# in-14driver.net
KiCad netlist of a schematic drawn in EAGLE
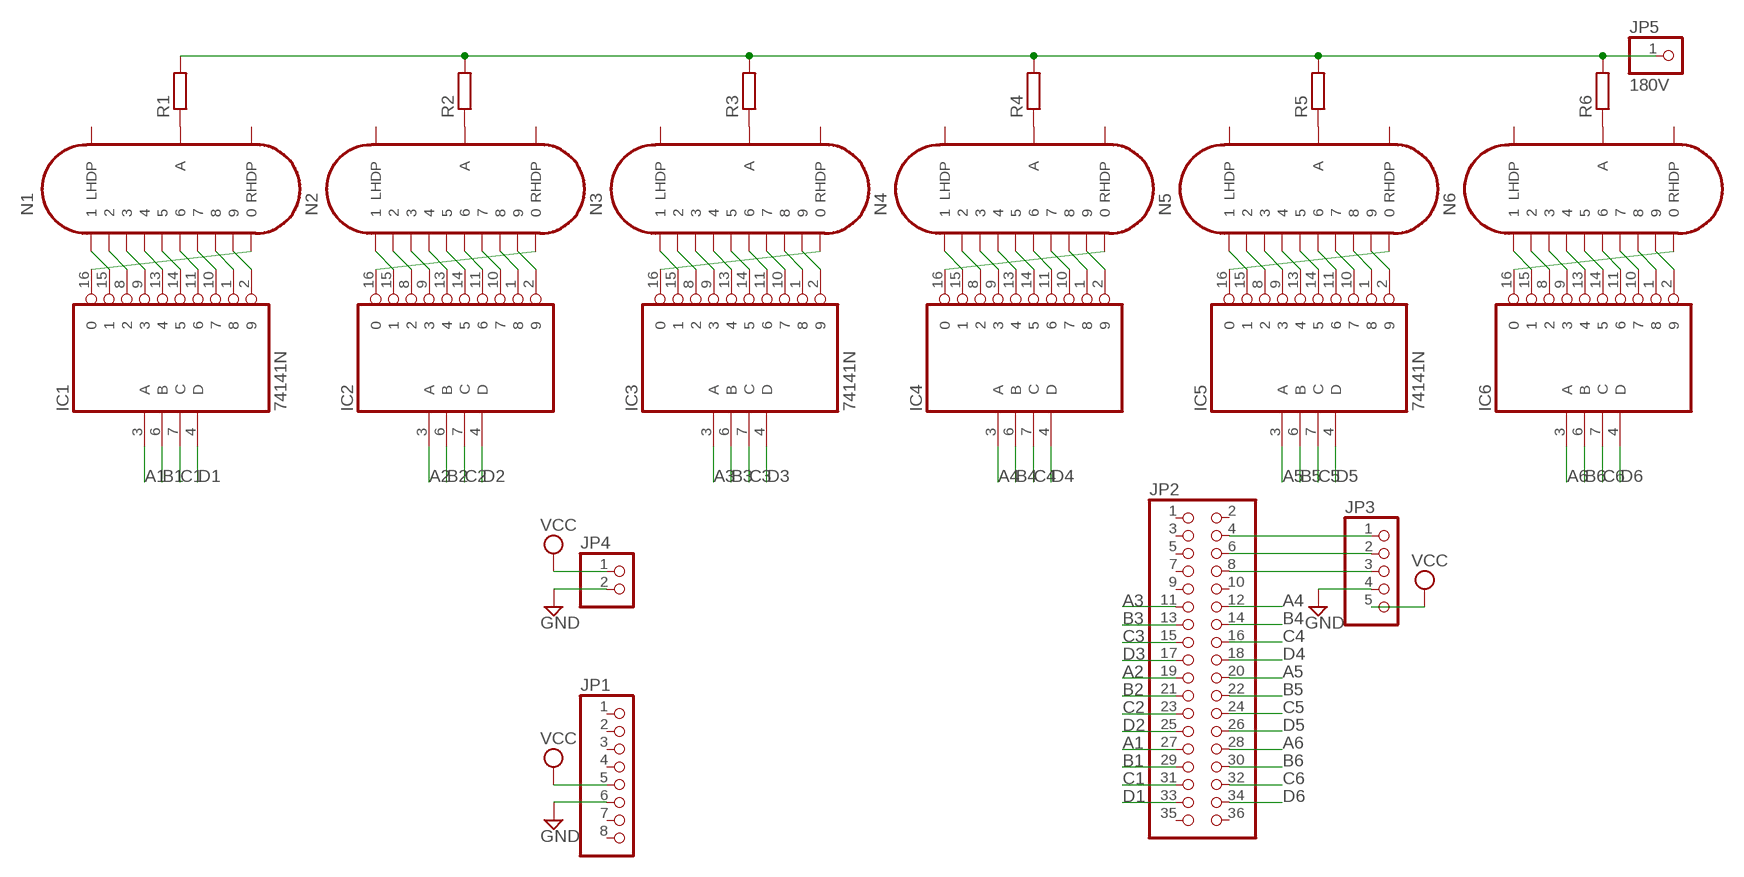
[diagram p0: schematic, sheet 1]

(export (version "E")
  (design (tool "Eeschema 10.0.6"))
  (components
    (comp (ref "IC1")
      (value "74141N")
      (footprint "eagle-import:DIL16")
      (libsource (lib "eagle-import") (part "74141N"))
    )
    (comp (ref "IC2")
      (value "74141N")
      (footprint "eagle-import:DIL16")
      (libsource (lib "eagle-import") (part "74141N"))
    )
    (comp (ref "IC3")
      (value "74141N")
      (footprint "eagle-import:DIL16")
      (libsource (lib "eagle-import") (part "74141N"))
    )
    (comp (ref "IC4")
      (value "74141N")
      (footprint "eagle-import:DIL16")
      (libsource (lib "eagle-import") (part "74141N"))
    )
    (comp (ref "IC5")
      (value "74141N")
      (footprint "eagle-import:DIL16")
      (libsource (lib "eagle-import") (part "74141N"))
    )
    (comp (ref "IC6")
      (value "74141N")
      (footprint "eagle-import:DIL16")
      (libsource (lib "eagle-import") (part "74141N"))
    )
    (comp (ref "JP1")
      (value "PINHD-1X8")
      (footprint "eagle-import:1X08")
      (libsource (lib "eagle-import") (part "PINHD-1X8"))
    )
    (comp (ref "JP2")
      (value "PINHD-2X18")
      (footprint "eagle-import:2X18")
      (libsource (lib "eagle-import") (part "PINHD-2X18"))
    )
    (comp (ref "JP3")
      (value "PINHD-1X5")
      (footprint "eagle-import:1X05")
      (libsource (lib "eagle-import") (part "PINHD-1X5"))
    )
    (comp (ref "JP4")
      (value "PINHD-1X2")
      (footprint "eagle-import:1X02")
      (libsource (lib "eagle-import") (part "PINHD-1X2"))
    )
    (comp (ref "JP5")
      (value "180V")
      (footprint "eagle-import:1X01")
      (libsource (lib "eagle-import") (part "PINHD-1X1"))
    )
    (comp (ref "N1")
      (value "IN-14")
      (footprint "eagle-import:IN-14")
      (libsource (lib "eagle-import") (part "IN-14"))
    )
    (comp (ref "N2")
      (value "IN-14")
      (footprint "eagle-import:IN-14")
      (libsource (lib "eagle-import") (part "IN-14"))
    )
    (comp (ref "N3")
      (value "IN-14")
      (footprint "eagle-import:IN-14")
      (libsource (lib "eagle-import") (part "IN-14"))
    )
    (comp (ref "N4")
      (value "IN-14")
      (footprint "eagle-import:IN-14")
      (libsource (lib "eagle-import") (part "IN-14"))
    )
    (comp (ref "N5")
      (value "IN-14")
      (footprint "eagle-import:IN-14")
      (libsource (lib "eagle-import") (part "IN-14"))
    )
    (comp (ref "N6")
      (value "IN-14")
      (footprint "eagle-import:IN-14")
      (libsource (lib "eagle-import") (part "IN-14"))
    )
    (comp (ref "R1")
      (value "R-EU_0207/10")
      (footprint "eagle-import:0207_10")
      (libsource (lib "eagle-import") (part "R-EU_0207/10"))
    )
    (comp (ref "R2")
      (value "R-EU_0207/10")
      (footprint "eagle-import:0207_10")
      (libsource (lib "eagle-import") (part "R-EU_0207/10"))
    )
    (comp (ref "R3")
      (value "R-EU_0207/10")
      (footprint "eagle-import:0207_10")
      (libsource (lib "eagle-import") (part "R-EU_0207/10"))
    )
    (comp (ref "R4")
      (value "R-EU_0207/10")
      (footprint "eagle-import:0207_10")
      (libsource (lib "eagle-import") (part "R-EU_0207/10"))
    )
    (comp (ref "R5")
      (value "R-EU_0207/10")
      (footprint "eagle-import:0207_10")
      (libsource (lib "eagle-import") (part "R-EU_0207/10"))
    )
    (comp (ref "R6")
      (value "R-EU_0207/10")
      (footprint "eagle-import:0207_10")
      (libsource (lib "eagle-import") (part "R-EU_0207/10"))
    )
  )
  (nets
    (net (code "1") (name "/A1") (class "Default")
      (node (ref "IC1") (pin "3") (pinfunction "A_3") (pintype "input"))
      (node (ref "JP2") (pin "27") (pinfunction "27_27") (pintype "passive"))
    )
    (net (code "2") (name "/A2") (class "Default")
      (node (ref "IC2") (pin "3") (pinfunction "A_3") (pintype "input"))
      (node (ref "JP2") (pin "19") (pinfunction "19_19") (pintype "passive"))
    )
    (net (code "3") (name "/A3") (class "Default")
      (node (ref "IC3") (pin "3") (pinfunction "A_3") (pintype "input"))
      (node (ref "JP2") (pin "11") (pinfunction "11_11") (pintype "passive"))
    )
    (net (code "4") (name "/A4") (class "Default")
      (node (ref "IC4") (pin "3") (pinfunction "A_3") (pintype "input"))
      (node (ref "JP2") (pin "12") (pinfunction "12_12") (pintype "passive"))
    )
    (net (code "5") (name "/A5") (class "Default")
      (node (ref "IC5") (pin "3") (pinfunction "A_3") (pintype "input"))
      (node (ref "JP2") (pin "20") (pinfunction "20_20") (pintype "passive"))
    )
    (net (code "6") (name "/A6") (class "Default")
      (node (ref "IC6") (pin "3") (pinfunction "A_3") (pintype "input"))
      (node (ref "JP2") (pin "28") (pinfunction "28_28") (pintype "passive"))
    )
    (net (code "7") (name "/B1") (class "Default")
      (node (ref "IC1") (pin "6") (pinfunction "B_6") (pintype "input"))
      (node (ref "JP2") (pin "29") (pinfunction "29_29") (pintype "passive"))
    )
    (net (code "8") (name "/B2") (class "Default")
      (node (ref "IC2") (pin "6") (pinfunction "B_6") (pintype "input"))
      (node (ref "JP2") (pin "21") (pinfunction "21_21") (pintype "passive"))
    )
    (net (code "9") (name "/B3") (class "Default")
      (node (ref "IC3") (pin "6") (pinfunction "B_6") (pintype "input"))
      (node (ref "JP2") (pin "13") (pinfunction "13_13") (pintype "passive"))
    )
    (net (code "10") (name "/B4") (class "Default")
      (node (ref "IC4") (pin "6") (pinfunction "B_6") (pintype "input"))
      (node (ref "JP2") (pin "14") (pinfunction "14_14") (pintype "passive"))
    )
    (net (code "11") (name "/B5") (class "Default")
      (node (ref "IC5") (pin "6") (pinfunction "B_6") (pintype "input"))
      (node (ref "JP2") (pin "22") (pinfunction "22_22") (pintype "passive"))
    )
    (net (code "12") (name "/B6") (class "Default")
      (node (ref "IC6") (pin "6") (pinfunction "B_6") (pintype "input"))
      (node (ref "JP2") (pin "30") (pinfunction "30_30") (pintype "passive"))
    )
    (net (code "13") (name "/C1") (class "Default")
      (node (ref "IC1") (pin "7") (pinfunction "C_7") (pintype "input"))
      (node (ref "JP2") (pin "31") (pinfunction "31_31") (pintype "passive"))
    )
    (net (code "14") (name "/C2") (class "Default")
      (node (ref "IC2") (pin "7") (pinfunction "C_7") (pintype "input"))
      (node (ref "JP2") (pin "23") (pinfunction "23_23") (pintype "passive"))
    )
    (net (code "15") (name "/C3") (class "Default")
      (node (ref "IC3") (pin "7") (pinfunction "C_7") (pintype "input"))
      (node (ref "JP2") (pin "15") (pinfunction "15_15") (pintype "passive"))
    )
    (net (code "16") (name "/C4") (class "Default")
      (node (ref "IC4") (pin "7") (pinfunction "C_7") (pintype "input"))
      (node (ref "JP2") (pin "16") (pinfunction "16_16") (pintype "passive"))
    )
    (net (code "17") (name "/C5") (class "Default")
      (node (ref "IC5") (pin "7") (pinfunction "C_7") (pintype "input"))
      (node (ref "JP2") (pin "24") (pinfunction "24_24") (pintype "passive"))
    )
    (net (code "18") (name "/C6") (class "Default")
      (node (ref "IC6") (pin "7") (pinfunction "C_7") (pintype "input"))
      (node (ref "JP2") (pin "32") (pinfunction "32_32") (pintype "passive"))
    )
    (net (code "19") (name "/D1") (class "Default")
      (node (ref "IC1") (pin "4") (pinfunction "D_4") (pintype "input"))
      (node (ref "JP2") (pin "33") (pinfunction "33_33") (pintype "passive"))
    )
    (net (code "20") (name "/D2") (class "Default")
      (node (ref "IC2") (pin "4") (pinfunction "D_4") (pintype "input"))
      (node (ref "JP2") (pin "25") (pinfunction "25_25") (pintype "passive"))
    )
    (net (code "21") (name "/D3") (class "Default")
      (node (ref "IC3") (pin "4") (pinfunction "D_4") (pintype "input"))
      (node (ref "JP2") (pin "17") (pinfunction "17_17") (pintype "passive"))
    )
    (net (code "22") (name "/D4") (class "Default")
      (node (ref "IC4") (pin "4") (pinfunction "D_4") (pintype "input"))
      (node (ref "JP2") (pin "18") (pinfunction "18_18") (pintype "passive"))
    )
    (net (code "23") (name "/D5") (class "Default")
      (node (ref "IC5") (pin "4") (pinfunction "D_4") (pintype "input"))
      (node (ref "JP2") (pin "26") (pinfunction "26_26") (pintype "passive"))
    )
    (net (code "24") (name "/D6") (class "Default")
      (node (ref "IC6") (pin "4") (pinfunction "D_4") (pintype "input"))
      (node (ref "JP2") (pin "34") (pinfunction "34_34") (pintype "passive"))
    )
    (net (code "25") (name "GND") (class "Default")
      (node (ref "JP1") (pin "6") (pinfunction "6_6") (pintype "passive"))
      (node (ref "JP3") (pin "4") (pinfunction "4_4") (pintype "passive"))
      (node (ref "JP4") (pin "2") (pinfunction "2_2") (pintype "passive"))
    )
    (net (code "26") (name "Net-(IC1A-0)") (class "Default")
      (node (ref "IC1") (pin "16") (pinfunction "0_16") (pintype "open_collector"))
      (node (ref "N1") (pin "1") (pinfunction "0_1") (pintype "bidirectional"))
    )
    (net (code "27") (name "Net-(IC1A-1)") (class "Default")
      (node (ref "IC1") (pin "15") (pinfunction "1_15") (pintype "open_collector"))
      (node (ref "N1") (pin "0") (pinfunction "1_0") (pintype "bidirectional"))
    )
    (net (code "28") (name "Net-(IC1A-2)") (class "Default")
      (node (ref "IC1") (pin "8") (pinfunction "2_8") (pintype "open_collector"))
      (node (ref "N1") (pin "9") (pinfunction "2_9") (pintype "bidirectional"))
    )
    (net (code "29") (name "Net-(IC1A-3)") (class "Default")
      (node (ref "IC1") (pin "9") (pinfunction "3_9") (pintype "open_collector"))
      (node (ref "N1") (pin "8") (pinfunction "3_8") (pintype "bidirectional"))
    )
    (net (code "30") (name "Net-(IC1A-4)") (class "Default")
      (node (ref "IC1") (pin "13") (pinfunction "4_13") (pintype "open_collector"))
      (node (ref "N1") (pin "7") (pinfunction "4_7") (pintype "bidirectional"))
    )
    (net (code "31") (name "Net-(IC1A-5)") (class "Default")
      (node (ref "IC1") (pin "14") (pinfunction "5_14") (pintype "open_collector"))
      (node (ref "N1") (pin "6") (pinfunction "5_6") (pintype "bidirectional"))
    )
    (net (code "32") (name "Net-(IC1A-6)") (class "Default")
      (node (ref "IC1") (pin "11") (pinfunction "6_11") (pintype "open_collector"))
      (node (ref "N1") (pin "5") (pinfunction "6_5") (pintype "bidirectional"))
    )
    (net (code "33") (name "Net-(IC1A-7)") (class "Default")
      (node (ref "IC1") (pin "10") (pinfunction "7_10") (pintype "open_collector"))
      (node (ref "N1") (pin "4") (pinfunction "7_4") (pintype "bidirectional"))
    )
    (net (code "34") (name "Net-(IC1A-8)") (class "Default")
      (node (ref "IC1") (pin "1") (pinfunction "8_1") (pintype "open_collector"))
      (node (ref "N1") (pin "3") (pinfunction "8_3") (pintype "bidirectional"))
    )
    (net (code "35") (name "Net-(IC1A-9)") (class "Default")
      (node (ref "IC1") (pin "2") (pinfunction "9_2") (pintype "open_collector"))
      (node (ref "N1") (pin "2") (pinfunction "9_2") (pintype "bidirectional"))
    )
    (net (code "36") (name "Net-(IC2A-0)") (class "Default")
      (node (ref "IC2") (pin "16") (pinfunction "0_16") (pintype "open_collector"))
      (node (ref "N2") (pin "1") (pinfunction "0_1") (pintype "bidirectional"))
    )
    (net (code "37") (name "Net-(IC2A-1)") (class "Default")
      (node (ref "IC2") (pin "15") (pinfunction "1_15") (pintype "open_collector"))
      (node (ref "N2") (pin "0") (pinfunction "1_0") (pintype "bidirectional"))
    )
    (net (code "38") (name "Net-(IC2A-2)") (class "Default")
      (node (ref "IC2") (pin "8") (pinfunction "2_8") (pintype "open_collector"))
      (node (ref "N2") (pin "9") (pinfunction "2_9") (pintype "bidirectional"))
    )
    (net (code "39") (name "Net-(IC2A-3)") (class "Default")
      (node (ref "IC2") (pin "9") (pinfunction "3_9") (pintype "open_collector"))
      (node (ref "N2") (pin "8") (pinfunction "3_8") (pintype "bidirectional"))
    )
    (net (code "40") (name "Net-(IC2A-4)") (class "Default")
      (node (ref "IC2") (pin "13") (pinfunction "4_13") (pintype "open_collector"))
      (node (ref "N2") (pin "7") (pinfunction "4_7") (pintype "bidirectional"))
    )
    (net (code "41") (name "Net-(IC2A-5)") (class "Default")
      (node (ref "IC2") (pin "14") (pinfunction "5_14") (pintype "open_collector"))
      (node (ref "N2") (pin "6") (pinfunction "5_6") (pintype "bidirectional"))
    )
    (net (code "42") (name "Net-(IC2A-6)") (class "Default")
      (node (ref "IC2") (pin "11") (pinfunction "6_11") (pintype "open_collector"))
      (node (ref "N2") (pin "5") (pinfunction "6_5") (pintype "bidirectional"))
    )
    (net (code "43") (name "Net-(IC2A-7)") (class "Default")
      (node (ref "IC2") (pin "10") (pinfunction "7_10") (pintype "open_collector"))
      (node (ref "N2") (pin "4") (pinfunction "7_4") (pintype "bidirectional"))
    )
    (net (code "44") (name "Net-(IC2A-8)") (class "Default")
      (node (ref "IC2") (pin "1") (pinfunction "8_1") (pintype "open_collector"))
      (node (ref "N2") (pin "3") (pinfunction "8_3") (pintype "bidirectional"))
    )
    (net (code "45") (name "Net-(IC2A-9)") (class "Default")
      (node (ref "IC2") (pin "2") (pinfunction "9_2") (pintype "open_collector"))
      (node (ref "N2") (pin "2") (pinfunction "9_2") (pintype "bidirectional"))
    )
    (net (code "46") (name "Net-(IC3A-0)") (class "Default")
      (node (ref "IC3") (pin "16") (pinfunction "0_16") (pintype "open_collector"))
      (node (ref "N3") (pin "1") (pinfunction "0_1") (pintype "bidirectional"))
    )
    (net (code "47") (name "Net-(IC3A-1)") (class "Default")
      (node (ref "IC3") (pin "15") (pinfunction "1_15") (pintype "open_collector"))
      (node (ref "N3") (pin "0") (pinfunction "1_0") (pintype "bidirectional"))
    )
    (net (code "48") (name "Net-(IC3A-2)") (class "Default")
      (node (ref "IC3") (pin "8") (pinfunction "2_8") (pintype "open_collector"))
      (node (ref "N3") (pin "9") (pinfunction "2_9") (pintype "bidirectional"))
    )
    (net (code "49") (name "Net-(IC3A-3)") (class "Default")
      (node (ref "IC3") (pin "9") (pinfunction "3_9") (pintype "open_collector"))
      (node (ref "N3") (pin "8") (pinfunction "3_8") (pintype "bidirectional"))
    )
    (net (code "50") (name "Net-(IC3A-4)") (class "Default")
      (node (ref "IC3") (pin "13") (pinfunction "4_13") (pintype "open_collector"))
      (node (ref "N3") (pin "7") (pinfunction "4_7") (pintype "bidirectional"))
    )
    (net (code "51") (name "Net-(IC3A-5)") (class "Default")
      (node (ref "IC3") (pin "14") (pinfunction "5_14") (pintype "open_collector"))
      (node (ref "N3") (pin "6") (pinfunction "5_6") (pintype "bidirectional"))
    )
    (net (code "52") (name "Net-(IC3A-6)") (class "Default")
      (node (ref "IC3") (pin "11") (pinfunction "6_11") (pintype "open_collector"))
      (node (ref "N3") (pin "5") (pinfunction "6_5") (pintype "bidirectional"))
    )
    (net (code "53") (name "Net-(IC3A-7)") (class "Default")
      (node (ref "IC3") (pin "10") (pinfunction "7_10") (pintype "open_collector"))
      (node (ref "N3") (pin "4") (pinfunction "7_4") (pintype "bidirectional"))
    )
    (net (code "54") (name "Net-(IC3A-8)") (class "Default")
      (node (ref "IC3") (pin "1") (pinfunction "8_1") (pintype "open_collector"))
      (node (ref "N3") (pin "3") (pinfunction "8_3") (pintype "bidirectional"))
    )
    (net (code "55") (name "Net-(IC3A-9)") (class "Default")
      (node (ref "IC3") (pin "2") (pinfunction "9_2") (pintype "open_collector"))
      (node (ref "N3") (pin "2") (pinfunction "9_2") (pintype "bidirectional"))
    )
    (net (code "56") (name "Net-(IC4A-0)") (class "Default")
      (node (ref "IC4") (pin "16") (pinfunction "0_16") (pintype "open_collector"))
      (node (ref "N4") (pin "1") (pinfunction "0_1") (pintype "bidirectional"))
    )
    (net (code "57") (name "Net-(IC4A-1)") (class "Default")
      (node (ref "IC4") (pin "15") (pinfunction "1_15") (pintype "open_collector"))
      (node (ref "N4") (pin "0") (pinfunction "1_0") (pintype "bidirectional"))
    )
    (net (code "58") (name "Net-(IC4A-2)") (class "Default")
      (node (ref "IC4") (pin "8") (pinfunction "2_8") (pintype "open_collector"))
      (node (ref "N4") (pin "9") (pinfunction "2_9") (pintype "bidirectional"))
    )
    (net (code "59") (name "Net-(IC4A-3)") (class "Default")
      (node (ref "IC4") (pin "9") (pinfunction "3_9") (pintype "open_collector"))
      (node (ref "N4") (pin "8") (pinfunction "3_8") (pintype "bidirectional"))
    )
    (net (code "60") (name "Net-(IC4A-4)") (class "Default")
      (node (ref "IC4") (pin "13") (pinfunction "4_13") (pintype "open_collector"))
      (node (ref "N4") (pin "7") (pinfunction "4_7") (pintype "bidirectional"))
    )
    (net (code "61") (name "Net-(IC4A-5)") (class "Default")
      (node (ref "IC4") (pin "14") (pinfunction "5_14") (pintype "open_collector"))
      (node (ref "N4") (pin "6") (pinfunction "5_6") (pintype "bidirectional"))
    )
    (net (code "62") (name "Net-(IC4A-6)") (class "Default")
      (node (ref "IC4") (pin "11") (pinfunction "6_11") (pintype "open_collector"))
      (node (ref "N4") (pin "5") (pinfunction "6_5") (pintype "bidirectional"))
    )
    (net (code "63") (name "Net-(IC4A-7)") (class "Default")
      (node (ref "IC4") (pin "10") (pinfunction "7_10") (pintype "open_collector"))
      (node (ref "N4") (pin "4") (pinfunction "7_4") (pintype "bidirectional"))
    )
    (net (code "64") (name "Net-(IC4A-8)") (class "Default")
      (node (ref "IC4") (pin "1") (pinfunction "8_1") (pintype "open_collector"))
      (node (ref "N4") (pin "3") (pinfunction "8_3") (pintype "bidirectional"))
    )
    (net (code "65") (name "Net-(IC4A-9)") (class "Default")
      (node (ref "IC4") (pin "2") (pinfunction "9_2") (pintype "open_collector"))
      (node (ref "N4") (pin "2") (pinfunction "9_2") (pintype "bidirectional"))
    )
    (net (code "66") (name "Net-(IC5A-0)") (class "Default")
      (node (ref "IC5") (pin "16") (pinfunction "0_16") (pintype "open_collector"))
      (node (ref "N5") (pin "1") (pinfunction "0_1") (pintype "bidirectional"))
    )
    (net (code "67") (name "Net-(IC5A-1)") (class "Default")
      (node (ref "IC5") (pin "15") (pinfunction "1_15") (pintype "open_collector"))
      (node (ref "N5") (pin "0") (pinfunction "1_0") (pintype "bidirectional"))
    )
    (net (code "68") (name "Net-(IC5A-2)") (class "Default")
      (node (ref "IC5") (pin "8") (pinfunction "2_8") (pintype "open_collector"))
      (node (ref "N5") (pin "9") (pinfunction "2_9") (pintype "bidirectional"))
    )
    (net (code "69") (name "Net-(IC5A-3)") (class "Default")
      (node (ref "IC5") (pin "9") (pinfunction "3_9") (pintype "open_collector"))
      (node (ref "N5") (pin "8") (pinfunction "3_8") (pintype "bidirectional"))
    )
    (net (code "70") (name "Net-(IC5A-4)") (class "Default")
      (node (ref "IC5") (pin "13") (pinfunction "4_13") (pintype "open_collector"))
      (node (ref "N5") (pin "7") (pinfunction "4_7") (pintype "bidirectional"))
    )
    (net (code "71") (name "Net-(IC5A-5)") (class "Default")
      (node (ref "IC5") (pin "14") (pinfunction "5_14") (pintype "open_collector"))
      (node (ref "N5") (pin "6") (pinfunction "5_6") (pintype "bidirectional"))
    )
    (net (code "72") (name "Net-(IC5A-6)") (class "Default")
      (node (ref "IC5") (pin "11") (pinfunction "6_11") (pintype "open_collector"))
      (node (ref "N5") (pin "5") (pinfunction "6_5") (pintype "bidirectional"))
    )
    (net (code "73") (name "Net-(IC5A-7)") (class "Default")
      (node (ref "IC5") (pin "10") (pinfunction "7_10") (pintype "open_collector"))
      (node (ref "N5") (pin "4") (pinfunction "7_4") (pintype "bidirectional"))
    )
    (net (code "74") (name "Net-(IC5A-8)") (class "Default")
      (node (ref "IC5") (pin "1") (pinfunction "8_1") (pintype "open_collector"))
      (node (ref "N5") (pin "3") (pinfunction "8_3") (pintype "bidirectional"))
    )
    (net (code "75") (name "Net-(IC5A-9)") (class "Default")
      (node (ref "IC5") (pin "2") (pinfunction "9_2") (pintype "open_collector"))
      (node (ref "N5") (pin "2") (pinfunction "9_2") (pintype "bidirectional"))
    )
    (net (code "76") (name "Net-(IC6A-0)") (class "Default")
      (node (ref "IC6") (pin "16") (pinfunction "0_16") (pintype "open_collector"))
      (node (ref "N6") (pin "1") (pinfunction "0_1") (pintype "bidirectional"))
    )
    (net (code "77") (name "Net-(IC6A-1)") (class "Default")
      (node (ref "IC6") (pin "15") (pinfunction "1_15") (pintype "open_collector"))
      (node (ref "N6") (pin "0") (pinfunction "1_0") (pintype "bidirectional"))
    )
    (net (code "78") (name "Net-(IC6A-2)") (class "Default")
      (node (ref "IC6") (pin "8") (pinfunction "2_8") (pintype "open_collector"))
      (node (ref "N6") (pin "9") (pinfunction "2_9") (pintype "bidirectional"))
    )
    (net (code "79") (name "Net-(IC6A-3)") (class "Default")
      (node (ref "IC6") (pin "9") (pinfunction "3_9") (pintype "open_collector"))
      (node (ref "N6") (pin "8") (pinfunction "3_8") (pintype "bidirectional"))
    )
    (net (code "80") (name "Net-(IC6A-4)") (class "Default")
      (node (ref "IC6") (pin "13") (pinfunction "4_13") (pintype "open_collector"))
      (node (ref "N6") (pin "7") (pinfunction "4_7") (pintype "bidirectional"))
    )
    (net (code "81") (name "Net-(IC6A-5)") (class "Default")
      (node (ref "IC6") (pin "14") (pinfunction "5_14") (pintype "open_collector"))
      (node (ref "N6") (pin "6") (pinfunction "5_6") (pintype "bidirectional"))
    )
    (net (code "82") (name "Net-(IC6A-6)") (class "Default")
      (node (ref "IC6") (pin "11") (pinfunction "6_11") (pintype "open_collector"))
      (node (ref "N6") (pin "5") (pinfunction "6_5") (pintype "bidirectional"))
    )
    (net (code "83") (name "Net-(IC6A-7)") (class "Default")
      (node (ref "IC6") (pin "10") (pinfunction "7_10") (pintype "open_collector"))
      (node (ref "N6") (pin "4") (pinfunction "7_4") (pintype "bidirectional"))
    )
    (net (code "84") (name "Net-(IC6A-8)") (class "Default")
      (node (ref "IC6") (pin "1") (pinfunction "8_1") (pintype "open_collector"))
      (node (ref "N6") (pin "3") (pinfunction "8_3") (pintype "bidirectional"))
    )
    (net (code "85") (name "Net-(IC6A-9)") (class "Default")
      (node (ref "IC6") (pin "2") (pinfunction "9_2") (pintype "open_collector"))
      (node (ref "N6") (pin "2") (pinfunction "9_2") (pintype "bidirectional"))
    )
    (net (code "86") (name "Net-(JP2-Pad4)") (class "Default")
      (node (ref "JP2") (pin "4") (pinfunction "4_4") (pintype "passive"))
      (node (ref "JP3") (pin "1") (pinfunction "1_1") (pintype "passive"))
    )
    (net (code "87") (name "Net-(JP2-Pad6)") (class "Default")
      (node (ref "JP2") (pin "6") (pinfunction "6_6") (pintype "passive"))
      (node (ref "JP3") (pin "2") (pinfunction "2_2") (pintype "passive"))
    )
    (net (code "88") (name "Net-(JP2-Pad8)") (class "Default")
      (node (ref "JP2") (pin "8") (pinfunction "8_8") (pintype "passive"))
      (node (ref "JP3") (pin "3") (pinfunction "3_3") (pintype "passive"))
    )
    (net (code "89") (name "Net-(JP5-Pad1)") (class "Default")
      (node (ref "JP5") (pin "1") (pinfunction "1_1") (pintype "passive"))
      (node (ref "R1") (pin "2") (pinfunction "2_2") (pintype "passive"))
      (node (ref "R2") (pin "2") (pinfunction "2_2") (pintype "passive"))
      (node (ref "R3") (pin "2") (pinfunction "2_2") (pintype "passive"))
      (node (ref "R4") (pin "2") (pinfunction "2_2") (pintype "passive"))
      (node (ref "R5") (pin "2") (pinfunction "2_2") (pintype "passive"))
      (node (ref "R6") (pin "2") (pinfunction "2_2") (pintype "passive"))
    )
    (net (code "90") (name "Net-(N1-PadA)") (class "Default")
      (node (ref "N1") (pin "A") (pinfunction "A_A") (pintype "bidirectional"))
      (node (ref "R1") (pin "1") (pinfunction "1_1") (pintype "passive"))
    )
    (net (code "91") (name "Net-(N2-PadA)") (class "Default")
      (node (ref "N2") (pin "A") (pinfunction "A_A") (pintype "bidirectional"))
      (node (ref "R2") (pin "1") (pinfunction "1_1") (pintype "passive"))
    )
    (net (code "92") (name "Net-(N3-PadA)") (class "Default")
      (node (ref "N3") (pin "A") (pinfunction "A_A") (pintype "bidirectional"))
      (node (ref "R3") (pin "1") (pinfunction "1_1") (pintype "passive"))
    )
    (net (code "93") (name "Net-(N4-PadA)") (class "Default")
      (node (ref "N4") (pin "A") (pinfunction "A_A") (pintype "bidirectional"))
      (node (ref "R4") (pin "1") (pinfunction "1_1") (pintype "passive"))
    )
    (net (code "94") (name "Net-(N5-PadA)") (class "Default")
      (node (ref "N5") (pin "A") (pinfunction "A_A") (pintype "bidirectional"))
      (node (ref "R5") (pin "1") (pinfunction "1_1") (pintype "passive"))
    )
    (net (code "95") (name "Net-(N6-PadA)") (class "Default")
      (node (ref "N6") (pin "A") (pinfunction "A_A") (pintype "bidirectional"))
      (node (ref "R6") (pin "1") (pinfunction "1_1") (pintype "passive"))
    )
    (net (code "96") (name "VCC") (class "Default")
      (node (ref "JP1") (pin "5") (pinfunction "5_5") (pintype "passive"))
      (node (ref "JP3") (pin "5") (pinfunction "5_5") (pintype "passive"))
      (node (ref "JP4") (pin "1") (pinfunction "1_1") (pintype "passive"))
    )
    (net (code "97") (name "unconnected-(JP1-Pad1)") (class "Default")
      (node (ref "JP1") (pin "1") (pinfunction "1_1") (pintype "passive"))
    )
    (net (code "98") (name "unconnected-(JP1-Pad2)") (class "Default")
      (node (ref "JP1") (pin "2") (pinfunction "2_2") (pintype "passive"))
    )
    (net (code "99") (name "unconnected-(JP1-Pad3)") (class "Default")
      (node (ref "JP1") (pin "3") (pinfunction "3_3") (pintype "passive"))
    )
    (net (code "100") (name "unconnected-(JP1-Pad4)") (class "Default")
      (node (ref "JP1") (pin "4") (pinfunction "4_4") (pintype "passive"))
    )
    (net (code "101") (name "unconnected-(JP1-Pad7)") (class "Default")
      (node (ref "JP1") (pin "7") (pinfunction "7_7") (pintype "passive"))
    )
    (net (code "102") (name "unconnected-(JP1-Pad8)") (class "Default")
      (node (ref "JP1") (pin "8") (pinfunction "8_8") (pintype "passive"))
    )
    (net (code "103") (name "unconnected-(JP2-Pad1)") (class "Default")
      (node (ref "JP2") (pin "1") (pinfunction "1_1") (pintype "passive"))
    )
    (net (code "104") (name "unconnected-(JP2-Pad2)") (class "Default")
      (node (ref "JP2") (pin "2") (pinfunction "2_2") (pintype "passive"))
    )
    (net (code "105") (name "unconnected-(JP2-Pad3)") (class "Default")
      (node (ref "JP2") (pin "3") (pinfunction "3_3") (pintype "passive"))
    )
    (net (code "106") (name "unconnected-(JP2-Pad5)") (class "Default")
      (node (ref "JP2") (pin "5") (pinfunction "5_5") (pintype "passive"))
    )
    (net (code "107") (name "unconnected-(JP2-Pad7)") (class "Default")
      (node (ref "JP2") (pin "7") (pinfunction "7_7") (pintype "passive"))
    )
    (net (code "108") (name "unconnected-(JP2-Pad9)") (class "Default")
      (node (ref "JP2") (pin "9") (pinfunction "9_9") (pintype "passive"))
    )
    (net (code "109") (name "unconnected-(JP2-Pad10)") (class "Default")
      (node (ref "JP2") (pin "10") (pinfunction "10_10") (pintype "passive"))
    )
    (net (code "110") (name "unconnected-(JP2-Pad35)") (class "Default")
      (node (ref "JP2") (pin "35") (pinfunction "35_35") (pintype "passive"))
    )
    (net (code "111") (name "unconnected-(JP2-Pad36)") (class "Default")
      (node (ref "JP2") (pin "36") (pinfunction "36_36") (pintype "passive"))
    )
    (net (code "112") (name "unconnected-(N1-PadLHDP)") (class "Default")
      (node (ref "N1") (pin "LHDP") (pinfunction "LHDP_LHDP") (pintype "bidirectional"))
    )
    (net (code "113") (name "unconnected-(N1-PadRHDP)") (class "Default")
      (node (ref "N1") (pin "RHDP") (pinfunction "RHDP_RHDP") (pintype "bidirectional"))
    )
    (net (code "114") (name "unconnected-(N2-PadLHDP)") (class "Default")
      (node (ref "N2") (pin "LHDP") (pinfunction "LHDP_LHDP") (pintype "bidirectional"))
    )
    (net (code "115") (name "unconnected-(N2-PadRHDP)") (class "Default")
      (node (ref "N2") (pin "RHDP") (pinfunction "RHDP_RHDP") (pintype "bidirectional"))
    )
    (net (code "116") (name "unconnected-(N3-PadLHDP)") (class "Default")
      (node (ref "N3") (pin "LHDP") (pinfunction "LHDP_LHDP") (pintype "bidirectional"))
    )
    (net (code "117") (name "unconnected-(N3-PadRHDP)") (class "Default")
      (node (ref "N3") (pin "RHDP") (pinfunction "RHDP_RHDP") (pintype "bidirectional"))
    )
    (net (code "118") (name "unconnected-(N4-PadLHDP)") (class "Default")
      (node (ref "N4") (pin "LHDP") (pinfunction "LHDP_LHDP") (pintype "bidirectional"))
    )
    (net (code "119") (name "unconnected-(N4-PadRHDP)") (class "Default")
      (node (ref "N4") (pin "RHDP") (pinfunction "RHDP_RHDP") (pintype "bidirectional"))
    )
    (net (code "120") (name "unconnected-(N5-PadLHDP)") (class "Default")
      (node (ref "N5") (pin "LHDP") (pinfunction "LHDP_LHDP") (pintype "bidirectional"))
    )
    (net (code "121") (name "unconnected-(N5-PadRHDP)") (class "Default")
      (node (ref "N5") (pin "RHDP") (pinfunction "RHDP_RHDP") (pintype "bidirectional"))
    )
    (net (code "122") (name "unconnected-(N6-PadLHDP)") (class "Default")
      (node (ref "N6") (pin "LHDP") (pinfunction "LHDP_LHDP") (pintype "bidirectional"))
    )
    (net (code "123") (name "unconnected-(N6-PadRHDP)") (class "Default")
      (node (ref "N6") (pin "RHDP") (pinfunction "RHDP_RHDP") (pintype "bidirectional"))
    )
  )
)
